# SCH_-_LED_Array.net
KiCad netlist of a schematic drawn in Altium Designer
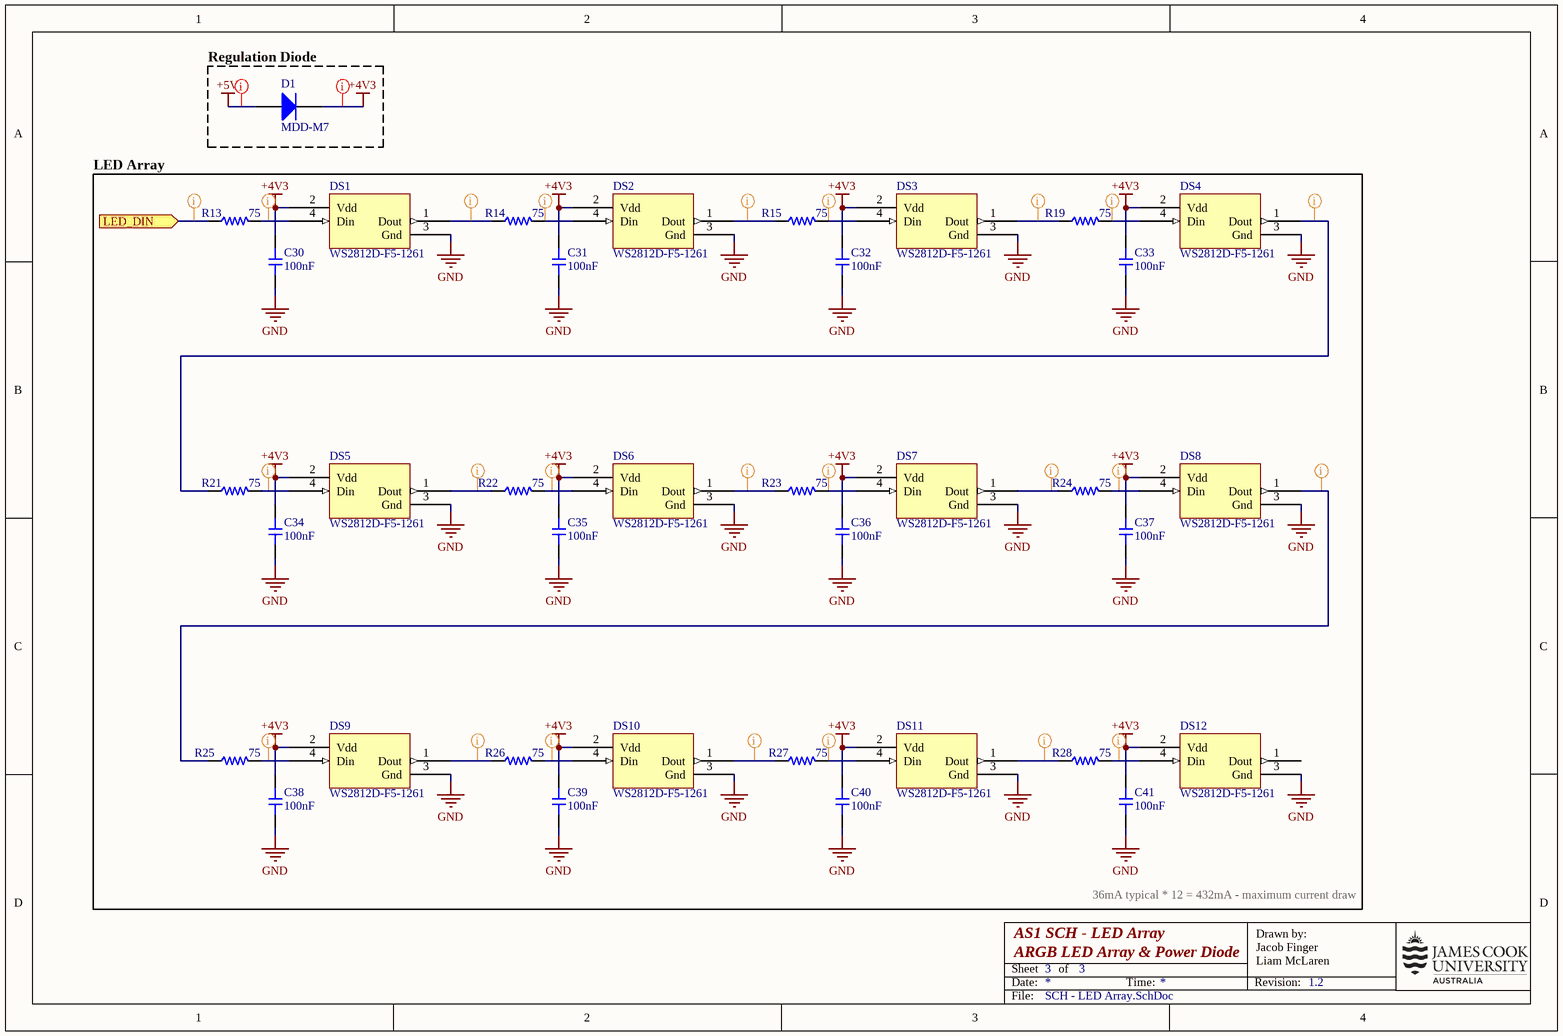
[diagram p0: SCH - LED Array.SchDoc]

(export (version "E")
  (design (tool "Eeschema 10.0.6"))
  (components
    (comp (ref "C30")
      (value "100nF")
      (footprint "CAP-0402")
      (description "Capacitor, Ceramic (MLCC), 100nF, ±10%, 16V, X7R, ±10%, SMD 0402")
      (fields
        (field (name "MANUFACTURER PART NUMBER") "CL05B104KO5NNNC")
        (field (name "MANUFACTURER") "Samsung Electro-Mechanics")
      )
      (libsource (lib "Finmac Systems") (part "GRM21BR61H106KE43L"))
    )
    (comp (ref "C31")
      (value "100nF")
      (footprint "CAP-0402")
      (description "Capacitor, Ceramic (MLCC), 100nF, ±10%, 16V, X7R, ±10%, SMD 0402")
      (fields
        (field (name "MANUFACTURER PART NUMBER") "CL05B104KO5NNNC")
        (field (name "MANUFACTURER") "Samsung Electro-Mechanics")
      )
      (libsource (lib "Finmac Systems") (part "GRM21BR61H106KE43L"))
    )
    (comp (ref "C32")
      (value "100nF")
      (footprint "CAP-0402")
      (description "Capacitor, Ceramic (MLCC), 100nF, ±10%, 16V, X7R, ±10%, SMD 0402")
      (fields
        (field (name "MANUFACTURER PART NUMBER") "CL05B104KO5NNNC")
        (field (name "MANUFACTURER") "Samsung Electro-Mechanics")
      )
      (libsource (lib "Finmac Systems") (part "GRM21BR61H106KE43L"))
    )
    (comp (ref "C33")
      (value "100nF")
      (footprint "CAP-0402")
      (description "Capacitor, Ceramic (MLCC), 100nF, ±10%, 16V, X7R, ±10%, SMD 0402")
      (fields
        (field (name "MANUFACTURER PART NUMBER") "CL05B104KO5NNNC")
        (field (name "MANUFACTURER") "Samsung Electro-Mechanics")
      )
      (libsource (lib "Finmac Systems") (part "GRM21BR61H106KE43L"))
    )
    (comp (ref "C34")
      (value "100nF")
      (footprint "CAP-0402")
      (description "Capacitor, Ceramic (MLCC), 100nF, ±10%, 16V, X7R, ±10%, SMD 0402")
      (fields
        (field (name "MANUFACTURER PART NUMBER") "CL05B104KO5NNNC")
        (field (name "MANUFACTURER") "Samsung Electro-Mechanics")
      )
      (libsource (lib "Finmac Systems") (part "GRM21BR61H106KE43L"))
    )
    (comp (ref "C35")
      (value "100nF")
      (footprint "CAP-0402")
      (description "Capacitor, Ceramic (MLCC), 100nF, ±10%, 16V, X7R, ±10%, SMD 0402")
      (fields
        (field (name "MANUFACTURER PART NUMBER") "CL05B104KO5NNNC")
        (field (name "MANUFACTURER") "Samsung Electro-Mechanics")
      )
      (libsource (lib "Finmac Systems") (part "GRM21BR61H106KE43L"))
    )
    (comp (ref "C36")
      (value "100nF")
      (footprint "CAP-0402")
      (description "Capacitor, Ceramic (MLCC), 100nF, ±10%, 16V, X7R, ±10%, SMD 0402")
      (fields
        (field (name "MANUFACTURER PART NUMBER") "CL05B104KO5NNNC")
        (field (name "MANUFACTURER") "Samsung Electro-Mechanics")
      )
      (libsource (lib "Finmac Systems") (part "GRM21BR61H106KE43L"))
    )
    (comp (ref "C37")
      (value "100nF")
      (footprint "CAP-0402")
      (description "Capacitor, Ceramic (MLCC), 100nF, ±10%, 16V, X7R, ±10%, SMD 0402")
      (fields
        (field (name "MANUFACTURER PART NUMBER") "CL05B104KO5NNNC")
        (field (name "MANUFACTURER") "Samsung Electro-Mechanics")
      )
      (libsource (lib "Finmac Systems") (part "GRM21BR61H106KE43L"))
    )
    (comp (ref "C38")
      (value "100nF")
      (footprint "CAP-0402")
      (description "Capacitor, Ceramic (MLCC), 100nF, ±10%, 16V, X7R, ±10%, SMD 0402")
      (fields
        (field (name "MANUFACTURER PART NUMBER") "CL05B104KO5NNNC")
        (field (name "MANUFACTURER") "Samsung Electro-Mechanics")
      )
      (libsource (lib "Finmac Systems") (part "GRM21BR61H106KE43L"))
    )
    (comp (ref "C39")
      (value "100nF")
      (footprint "CAP-0402")
      (description "Capacitor, Ceramic (MLCC), 100nF, ±10%, 16V, X7R, ±10%, SMD 0402")
      (fields
        (field (name "MANUFACTURER PART NUMBER") "CL05B104KO5NNNC")
        (field (name "MANUFACTURER") "Samsung Electro-Mechanics")
      )
      (libsource (lib "Finmac Systems") (part "GRM21BR61H106KE43L"))
    )
    (comp (ref "C40")
      (value "100nF")
      (footprint "CAP-0402")
      (description "Capacitor, Ceramic (MLCC), 100nF, ±10%, 16V, X7R, ±10%, SMD 0402")
      (fields
        (field (name "MANUFACTURER PART NUMBER") "CL05B104KO5NNNC")
        (field (name "MANUFACTURER") "Samsung Electro-Mechanics")
      )
      (libsource (lib "Finmac Systems") (part "GRM21BR61H106KE43L"))
    )
    (comp (ref "C41")
      (value "100nF")
      (footprint "CAP-0402")
      (description "Capacitor, Ceramic (MLCC), 100nF, ±10%, 16V, X7R, ±10%, SMD 0402")
      (fields
        (field (name "MANUFACTURER PART NUMBER") "CL05B104KO5NNNC")
        (field (name "MANUFACTURER") "Samsung Electro-Mechanics")
      )
      (libsource (lib "Finmac Systems") (part "GRM21BR61H106KE43L"))
    )
    (comp (ref "D1")
      (value "MDD-M7")
      (footprint "DIOM4227X24M")
      (description "General purpose rectifier, 1.0 A, 1 kV, DO-214AC SMD")
      (fields (field (name "MANUFACTURER PART NUMBER") "M7") (field (name "JLCPCB PART") "C95872"))
      (libsource (lib "James Cook University") (part "Diode"))
    )
    (comp (ref "DS1")
      (value "WS2812D-F5-1261")
      (footprint "WS2812D-F5-1261-Footprint-1")
      (description "Through-hole addressable RGB LED, 5mm")
      (libsource (lib "SCH_LIB_Assignment1") (part "CMP-010-0002-2"))
    )
    (comp (ref "DS2")
      (value "WS2812D-F5-1261")
      (footprint "WS2812D-F5-1261-Footprint-1")
      (description "Through-hole addressable RGB LED, 5mm")
      (libsource (lib "SCH_LIB_Assignment1") (part "CMP-010-0002-2"))
    )
    (comp (ref "DS3")
      (value "WS2812D-F5-1261")
      (footprint "WS2812D-F5-1261-Footprint-1")
      (description "Through-hole addressable RGB LED, 5mm")
      (libsource (lib "SCH_LIB_Assignment1") (part "CMP-010-0002-2"))
    )
    (comp (ref "DS4")
      (value "WS2812D-F5-1261")
      (footprint "WS2812D-F5-1261-Footprint-1")
      (description "Through-hole addressable RGB LED, 5mm")
      (libsource (lib "SCH_LIB_Assignment1") (part "CMP-010-0002-2"))
    )
    (comp (ref "DS5")
      (value "WS2812D-F5-1261")
      (footprint "WS2812D-F5-1261-Footprint-1")
      (description "Through-hole addressable RGB LED, 5mm")
      (libsource (lib "SCH_LIB_Assignment1") (part "CMP-010-0002-2"))
    )
    (comp (ref "DS6")
      (value "WS2812D-F5-1261")
      (footprint "WS2812D-F5-1261-Footprint-1")
      (description "Through-hole addressable RGB LED, 5mm")
      (libsource (lib "SCH_LIB_Assignment1") (part "CMP-010-0002-2"))
    )
    (comp (ref "DS7")
      (value "WS2812D-F5-1261")
      (footprint "WS2812D-F5-1261-Footprint-1")
      (description "Through-hole addressable RGB LED, 5mm")
      (libsource (lib "SCH_LIB_Assignment1") (part "CMP-010-0002-2"))
    )
    (comp (ref "DS8")
      (value "WS2812D-F5-1261")
      (footprint "WS2812D-F5-1261-Footprint-1")
      (description "Through-hole addressable RGB LED, 5mm")
      (libsource (lib "SCH_LIB_Assignment1") (part "CMP-010-0002-2"))
    )
    (comp (ref "DS9")
      (value "WS2812D-F5-1261")
      (footprint "WS2812D-F5-1261-Footprint-1")
      (description "Through-hole addressable RGB LED, 5mm")
      (libsource (lib "SCH_LIB_Assignment1") (part "CMP-010-0002-2"))
    )
    (comp (ref "DS10")
      (value "WS2812D-F5-1261")
      (footprint "WS2812D-F5-1261-Footprint-1")
      (description "Through-hole addressable RGB LED, 5mm")
      (libsource (lib "SCH_LIB_Assignment1") (part "CMP-010-0002-2"))
    )
    (comp (ref "DS11")
      (value "WS2812D-F5-1261")
      (footprint "WS2812D-F5-1261-Footprint-1")
      (description "Through-hole addressable RGB LED, 5mm")
      (libsource (lib "SCH_LIB_Assignment1") (part "CMP-010-0002-2"))
    )
    (comp (ref "DS12")
      (value "WS2812D-F5-1261")
      (footprint "WS2812D-F5-1261-Footprint-1")
      (description "Through-hole addressable RGB LED, 5mm")
      (libsource (lib "SCH_LIB_Assignment1") (part "CMP-010-0002-2"))
    )
    (comp (ref "R13")
      (value "75")
      (footprint "RES-0603")
      (description "Resistor, 75Ω, ±1%, 100mW, 75V, ±200ppm/℃, -55℃~+155℃, SMD 0603")
      (fields (field (name "MANUFACTURER PART NUMBER") "0603WAF750JT5E") (field (name "TOLERANCE") "1%"))
      (libsource (lib "Finmac Systems") (part "1206W4F7500T5E"))
    )
    (comp (ref "R14")
      (value "75")
      (footprint "RES-0603")
      (description "Resistor, 75Ω, ±1%, 100mW, 75V, ±200ppm/℃, -55℃~+155℃, SMD 0603")
      (fields (field (name "MANUFACTURER PART NUMBER") "0603WAF750JT5E") (field (name "TOLERANCE") "1%"))
      (libsource (lib "Finmac Systems") (part "1206W4F7500T5E"))
    )
    (comp (ref "R15")
      (value "75")
      (footprint "RES-0603")
      (description "Resistor, 75Ω, ±1%, 100mW, 75V, ±200ppm/℃, -55℃~+155℃, SMD 0603")
      (fields (field (name "MANUFACTURER PART NUMBER") "0603WAF750JT5E") (field (name "TOLERANCE") "1%"))
      (libsource (lib "Finmac Systems") (part "1206W4F7500T5E"))
    )
    (comp (ref "R19")
      (value "75")
      (footprint "RES-0603")
      (description "Resistor, 75Ω, ±1%, 100mW, 75V, ±200ppm/℃, -55℃~+155℃, SMD 0603")
      (fields (field (name "MANUFACTURER PART NUMBER") "0603WAF750JT5E") (field (name "TOLERANCE") "1%"))
      (libsource (lib "Finmac Systems") (part "1206W4F7500T5E"))
    )
    (comp (ref "R21")
      (value "75")
      (footprint "RES-0603")
      (description "Resistor, 75Ω, ±1%, 100mW, 75V, ±200ppm/℃, -55℃~+155℃, SMD 0603")
      (fields (field (name "MANUFACTURER PART NUMBER") "0603WAF750JT5E") (field (name "TOLERANCE") "1%"))
      (libsource (lib "Finmac Systems") (part "1206W4F7500T5E"))
    )
    (comp (ref "R22")
      (value "75")
      (footprint "RES-0603")
      (description "Resistor, 75Ω, ±1%, 100mW, 75V, ±200ppm/℃, -55℃~+155℃, SMD 0603")
      (fields (field (name "MANUFACTURER PART NUMBER") "0603WAF750JT5E") (field (name "TOLERANCE") "1%"))
      (libsource (lib "Finmac Systems") (part "1206W4F7500T5E"))
    )
    (comp (ref "R23")
      (value "75")
      (footprint "RES-0603")
      (description "Resistor, 75Ω, ±1%, 100mW, 75V, ±200ppm/℃, -55℃~+155℃, SMD 0603")
      (fields (field (name "MANUFACTURER PART NUMBER") "0603WAF750JT5E") (field (name "TOLERANCE") "1%"))
      (libsource (lib "Finmac Systems") (part "1206W4F7500T5E"))
    )
    (comp (ref "R24")
      (value "75")
      (footprint "RES-0603")
      (description "Resistor, 75Ω, ±1%, 100mW, 75V, ±200ppm/℃, -55℃~+155℃, SMD 0603")
      (fields (field (name "MANUFACTURER PART NUMBER") "0603WAF750JT5E") (field (name "TOLERANCE") "1%"))
      (libsource (lib "Finmac Systems") (part "1206W4F7500T5E"))
    )
    (comp (ref "R25")
      (value "75")
      (footprint "RES-0603")
      (description "Resistor, 75Ω, ±1%, 100mW, 75V, ±200ppm/℃, -55℃~+155℃, SMD 0603")
      (fields (field (name "MANUFACTURER PART NUMBER") "0603WAF750JT5E") (field (name "TOLERANCE") "1%"))
      (libsource (lib "Finmac Systems") (part "1206W4F7500T5E"))
    )
    (comp (ref "R26")
      (value "75")
      (footprint "RES-0603")
      (description "Resistor, 75Ω, ±1%, 100mW, 75V, ±200ppm/℃, -55℃~+155℃, SMD 0603")
      (fields (field (name "MANUFACTURER PART NUMBER") "0603WAF750JT5E") (field (name "TOLERANCE") "1%"))
      (libsource (lib "Finmac Systems") (part "1206W4F7500T5E"))
    )
    (comp (ref "R27")
      (value "75")
      (footprint "RES-0603")
      (description "Resistor, 75Ω, ±1%, 100mW, 75V, ±200ppm/℃, -55℃~+155℃, SMD 0603")
      (fields (field (name "MANUFACTURER PART NUMBER") "0603WAF750JT5E") (field (name "TOLERANCE") "1%"))
      (libsource (lib "Finmac Systems") (part "1206W4F7500T5E"))
    )
    (comp (ref "R28")
      (value "75")
      (footprint "RES-0603")
      (description "Resistor, 75Ω, ±1%, 100mW, 75V, ±200ppm/℃, -55℃~+155℃, SMD 0603")
      (fields (field (name "MANUFACTURER PART NUMBER") "0603WAF750JT5E") (field (name "TOLERANCE") "1%"))
      (libsource (lib "Finmac Systems") (part "1206W4F7500T5E"))
    )
  )
  (nets
    (net (code "1") (name "+4V3") (class "Default")
      (node (ref "C30") (pin "2") (pinfunction "2_2") (pintype "passive"))
      (node (ref "C31") (pin "2") (pinfunction "2_2") (pintype "passive"))
      (node (ref "C32") (pin "2") (pinfunction "2_2") (pintype "passive"))
      (node (ref "C33") (pin "2") (pinfunction "2_2") (pintype "passive"))
      (node (ref "C34") (pin "2") (pinfunction "2_2") (pintype "passive"))
      (node (ref "C35") (pin "2") (pinfunction "2_2") (pintype "passive"))
      (node (ref "C36") (pin "2") (pinfunction "2_2") (pintype "passive"))
      (node (ref "C37") (pin "2") (pinfunction "2_2") (pintype "passive"))
      (node (ref "C38") (pin "2") (pinfunction "2_2") (pintype "passive"))
      (node (ref "C39") (pin "2") (pinfunction "2_2") (pintype "passive"))
      (node (ref "C40") (pin "2") (pinfunction "2_2") (pintype "passive"))
      (node (ref "C41") (pin "2") (pinfunction "2_2") (pintype "passive"))
      (node (ref "D1") (pin "1") (pinfunction "1_1") (pintype "power_in"))
      (node (ref "DS1") (pin "2") (pinfunction "Vdd_2") (pintype "power_in"))
      (node (ref "DS10") (pin "2") (pinfunction "Vdd_2") (pintype "power_in"))
      (node (ref "DS11") (pin "2") (pinfunction "Vdd_2") (pintype "power_in"))
      (node (ref "DS12") (pin "2") (pinfunction "Vdd_2") (pintype "power_in"))
      (node (ref "DS2") (pin "2") (pinfunction "Vdd_2") (pintype "power_in"))
      (node (ref "DS3") (pin "2") (pinfunction "Vdd_2") (pintype "power_in"))
      (node (ref "DS4") (pin "2") (pinfunction "Vdd_2") (pintype "power_in"))
      (node (ref "DS5") (pin "2") (pinfunction "Vdd_2") (pintype "power_in"))
      (node (ref "DS6") (pin "2") (pinfunction "Vdd_2") (pintype "power_in"))
      (node (ref "DS7") (pin "2") (pinfunction "Vdd_2") (pintype "power_in"))
      (node (ref "DS8") (pin "2") (pinfunction "Vdd_2") (pintype "power_in"))
      (node (ref "DS9") (pin "2") (pinfunction "Vdd_2") (pintype "power_in"))
    )
    (net (code "2") (name "+5V") (class "Default")
      (node (ref "D1") (pin "2") (pinfunction "2_2") (pintype "power_in"))
    )
    (net (code "3") (name "/LED_DIN") (class "Default")
      (node (ref "R13") (pin "1") (pinfunction "1_1") (pintype "passive"))
    )
    (net (code "4") (name "GND") (class "Default")
      (node (ref "C30") (pin "1") (pinfunction "1_1") (pintype "passive"))
      (node (ref "C31") (pin "1") (pinfunction "1_1") (pintype "passive"))
      (node (ref "C32") (pin "1") (pinfunction "1_1") (pintype "passive"))
      (node (ref "C33") (pin "1") (pinfunction "1_1") (pintype "passive"))
      (node (ref "C34") (pin "1") (pinfunction "1_1") (pintype "passive"))
      (node (ref "C35") (pin "1") (pinfunction "1_1") (pintype "passive"))
      (node (ref "C36") (pin "1") (pinfunction "1_1") (pintype "passive"))
      (node (ref "C37") (pin "1") (pinfunction "1_1") (pintype "passive"))
      (node (ref "C38") (pin "1") (pinfunction "1_1") (pintype "passive"))
      (node (ref "C39") (pin "1") (pinfunction "1_1") (pintype "passive"))
      (node (ref "C40") (pin "1") (pinfunction "1_1") (pintype "passive"))
      (node (ref "C41") (pin "1") (pinfunction "1_1") (pintype "passive"))
      (node (ref "DS1") (pin "3") (pinfunction "Gnd_3") (pintype "power_in"))
      (node (ref "DS10") (pin "3") (pinfunction "Gnd_3") (pintype "power_in"))
      (node (ref "DS11") (pin "3") (pinfunction "Gnd_3") (pintype "power_in"))
      (node (ref "DS12") (pin "3") (pinfunction "Gnd_3") (pintype "power_in"))
      (node (ref "DS2") (pin "3") (pinfunction "Gnd_3") (pintype "power_in"))
      (node (ref "DS3") (pin "3") (pinfunction "Gnd_3") (pintype "power_in"))
      (node (ref "DS4") (pin "3") (pinfunction "Gnd_3") (pintype "power_in"))
      (node (ref "DS5") (pin "3") (pinfunction "Gnd_3") (pintype "power_in"))
      (node (ref "DS6") (pin "3") (pinfunction "Gnd_3") (pintype "power_in"))
      (node (ref "DS7") (pin "3") (pinfunction "Gnd_3") (pintype "power_in"))
      (node (ref "DS8") (pin "3") (pinfunction "Gnd_3") (pintype "power_in"))
      (node (ref "DS9") (pin "3") (pinfunction "Gnd_3") (pintype "power_in"))
    )
    (net (code "5") (name "Net-(DS1-Din)") (class "Default")
      (node (ref "DS1") (pin "4") (pinfunction "Din_4") (pintype "input"))
      (node (ref "R13") (pin "2") (pinfunction "2_2") (pintype "passive"))
    )
    (net (code "6") (name "Net-(DS1-Dout)") (class "Default")
      (node (ref "DS1") (pin "1") (pinfunction "Dout_1") (pintype "output"))
      (node (ref "R14") (pin "1") (pinfunction "1_1") (pintype "passive"))
    )
    (net (code "7") (name "Net-(DS2-Din)") (class "Default")
      (node (ref "DS2") (pin "4") (pinfunction "Din_4") (pintype "input"))
      (node (ref "R14") (pin "2") (pinfunction "2_2") (pintype "passive"))
    )
    (net (code "8") (name "Net-(DS2-Dout)") (class "Default")
      (node (ref "DS2") (pin "1") (pinfunction "Dout_1") (pintype "output"))
      (node (ref "R15") (pin "1") (pinfunction "1_1") (pintype "passive"))
    )
    (net (code "9") (name "Net-(DS3-Din)") (class "Default")
      (node (ref "DS3") (pin "4") (pinfunction "Din_4") (pintype "input"))
      (node (ref "R15") (pin "2") (pinfunction "2_2") (pintype "passive"))
    )
    (net (code "10") (name "Net-(DS3-Dout)") (class "Default")
      (node (ref "DS3") (pin "1") (pinfunction "Dout_1") (pintype "output"))
      (node (ref "R19") (pin "1") (pinfunction "1_1") (pintype "passive"))
    )
    (net (code "11") (name "Net-(DS4-Din)") (class "Default")
      (node (ref "DS4") (pin "4") (pinfunction "Din_4") (pintype "input"))
      (node (ref "R19") (pin "2") (pinfunction "2_2") (pintype "passive"))
    )
    (net (code "12") (name "Net-(DS4-Dout)") (class "Default")
      (node (ref "DS4") (pin "1") (pinfunction "Dout_1") (pintype "output"))
      (node (ref "R21") (pin "1") (pinfunction "1_1") (pintype "passive"))
    )
    (net (code "13") (name "Net-(DS5-Din)") (class "Default")
      (node (ref "DS5") (pin "4") (pinfunction "Din_4") (pintype "input"))
      (node (ref "R21") (pin "2") (pinfunction "2_2") (pintype "passive"))
    )
    (net (code "14") (name "Net-(DS5-Dout)") (class "Default")
      (node (ref "DS5") (pin "1") (pinfunction "Dout_1") (pintype "output"))
      (node (ref "R22") (pin "1") (pinfunction "1_1") (pintype "passive"))
    )
    (net (code "15") (name "Net-(DS6-Din)") (class "Default")
      (node (ref "DS6") (pin "4") (pinfunction "Din_4") (pintype "input"))
      (node (ref "R22") (pin "2") (pinfunction "2_2") (pintype "passive"))
    )
    (net (code "16") (name "Net-(DS6-Dout)") (class "Default")
      (node (ref "DS6") (pin "1") (pinfunction "Dout_1") (pintype "output"))
      (node (ref "R23") (pin "1") (pinfunction "1_1") (pintype "passive"))
    )
    (net (code "17") (name "Net-(DS7-Din)") (class "Default")
      (node (ref "DS7") (pin "4") (pinfunction "Din_4") (pintype "input"))
      (node (ref "R23") (pin "2") (pinfunction "2_2") (pintype "passive"))
    )
    (net (code "18") (name "Net-(DS7-Dout)") (class "Default")
      (node (ref "DS7") (pin "1") (pinfunction "Dout_1") (pintype "output"))
      (node (ref "R24") (pin "1") (pinfunction "1_1") (pintype "passive"))
    )
    (net (code "19") (name "Net-(DS8-Din)") (class "Default")
      (node (ref "DS8") (pin "4") (pinfunction "Din_4") (pintype "input"))
      (node (ref "R24") (pin "2") (pinfunction "2_2") (pintype "passive"))
    )
    (net (code "20") (name "Net-(DS8-Dout)") (class "Default")
      (node (ref "DS8") (pin "1") (pinfunction "Dout_1") (pintype "output"))
      (node (ref "R25") (pin "1") (pinfunction "1_1") (pintype "passive"))
    )
    (net (code "21") (name "Net-(DS9-Din)") (class "Default")
      (node (ref "DS9") (pin "4") (pinfunction "Din_4") (pintype "input"))
      (node (ref "R25") (pin "2") (pinfunction "2_2") (pintype "passive"))
    )
    (net (code "22") (name "Net-(DS9-Dout)") (class "Default")
      (node (ref "DS9") (pin "1") (pinfunction "Dout_1") (pintype "output"))
      (node (ref "R26") (pin "1") (pinfunction "1_1") (pintype "passive"))
    )
    (net (code "23") (name "Net-(DS10-Din)") (class "Default")
      (node (ref "DS10") (pin "4") (pinfunction "Din_4") (pintype "input"))
      (node (ref "R26") (pin "2") (pinfunction "2_2") (pintype "passive"))
    )
    (net (code "24") (name "Net-(DS10-Dout)") (class "Default")
      (node (ref "DS10") (pin "1") (pinfunction "Dout_1") (pintype "output"))
      (node (ref "R27") (pin "1") (pinfunction "1_1") (pintype "passive"))
    )
    (net (code "25") (name "Net-(DS11-Din)") (class "Default")
      (node (ref "DS11") (pin "4") (pinfunction "Din_4") (pintype "input"))
      (node (ref "R27") (pin "2") (pinfunction "2_2") (pintype "passive"))
    )
    (net (code "26") (name "Net-(DS11-Dout)") (class "Default")
      (node (ref "DS11") (pin "1") (pinfunction "Dout_1") (pintype "output"))
      (node (ref "R28") (pin "1") (pinfunction "1_1") (pintype "passive"))
    )
    (net (code "27") (name "Net-(DS12-Din)") (class "Default")
      (node (ref "DS12") (pin "4") (pinfunction "Din_4") (pintype "input"))
      (node (ref "R28") (pin "2") (pinfunction "2_2") (pintype "passive"))
    )
    (net (code "28") (name "unconnected-(DS12-Dout-Pad1)") (class "Default")
      (node (ref "DS12") (pin "1") (pinfunction "Dout_1") (pintype "output"))
    )
  )
)
